# P21_HDMI_OUT.net
KiCad netlist of a schematic drawn in Altium Designer
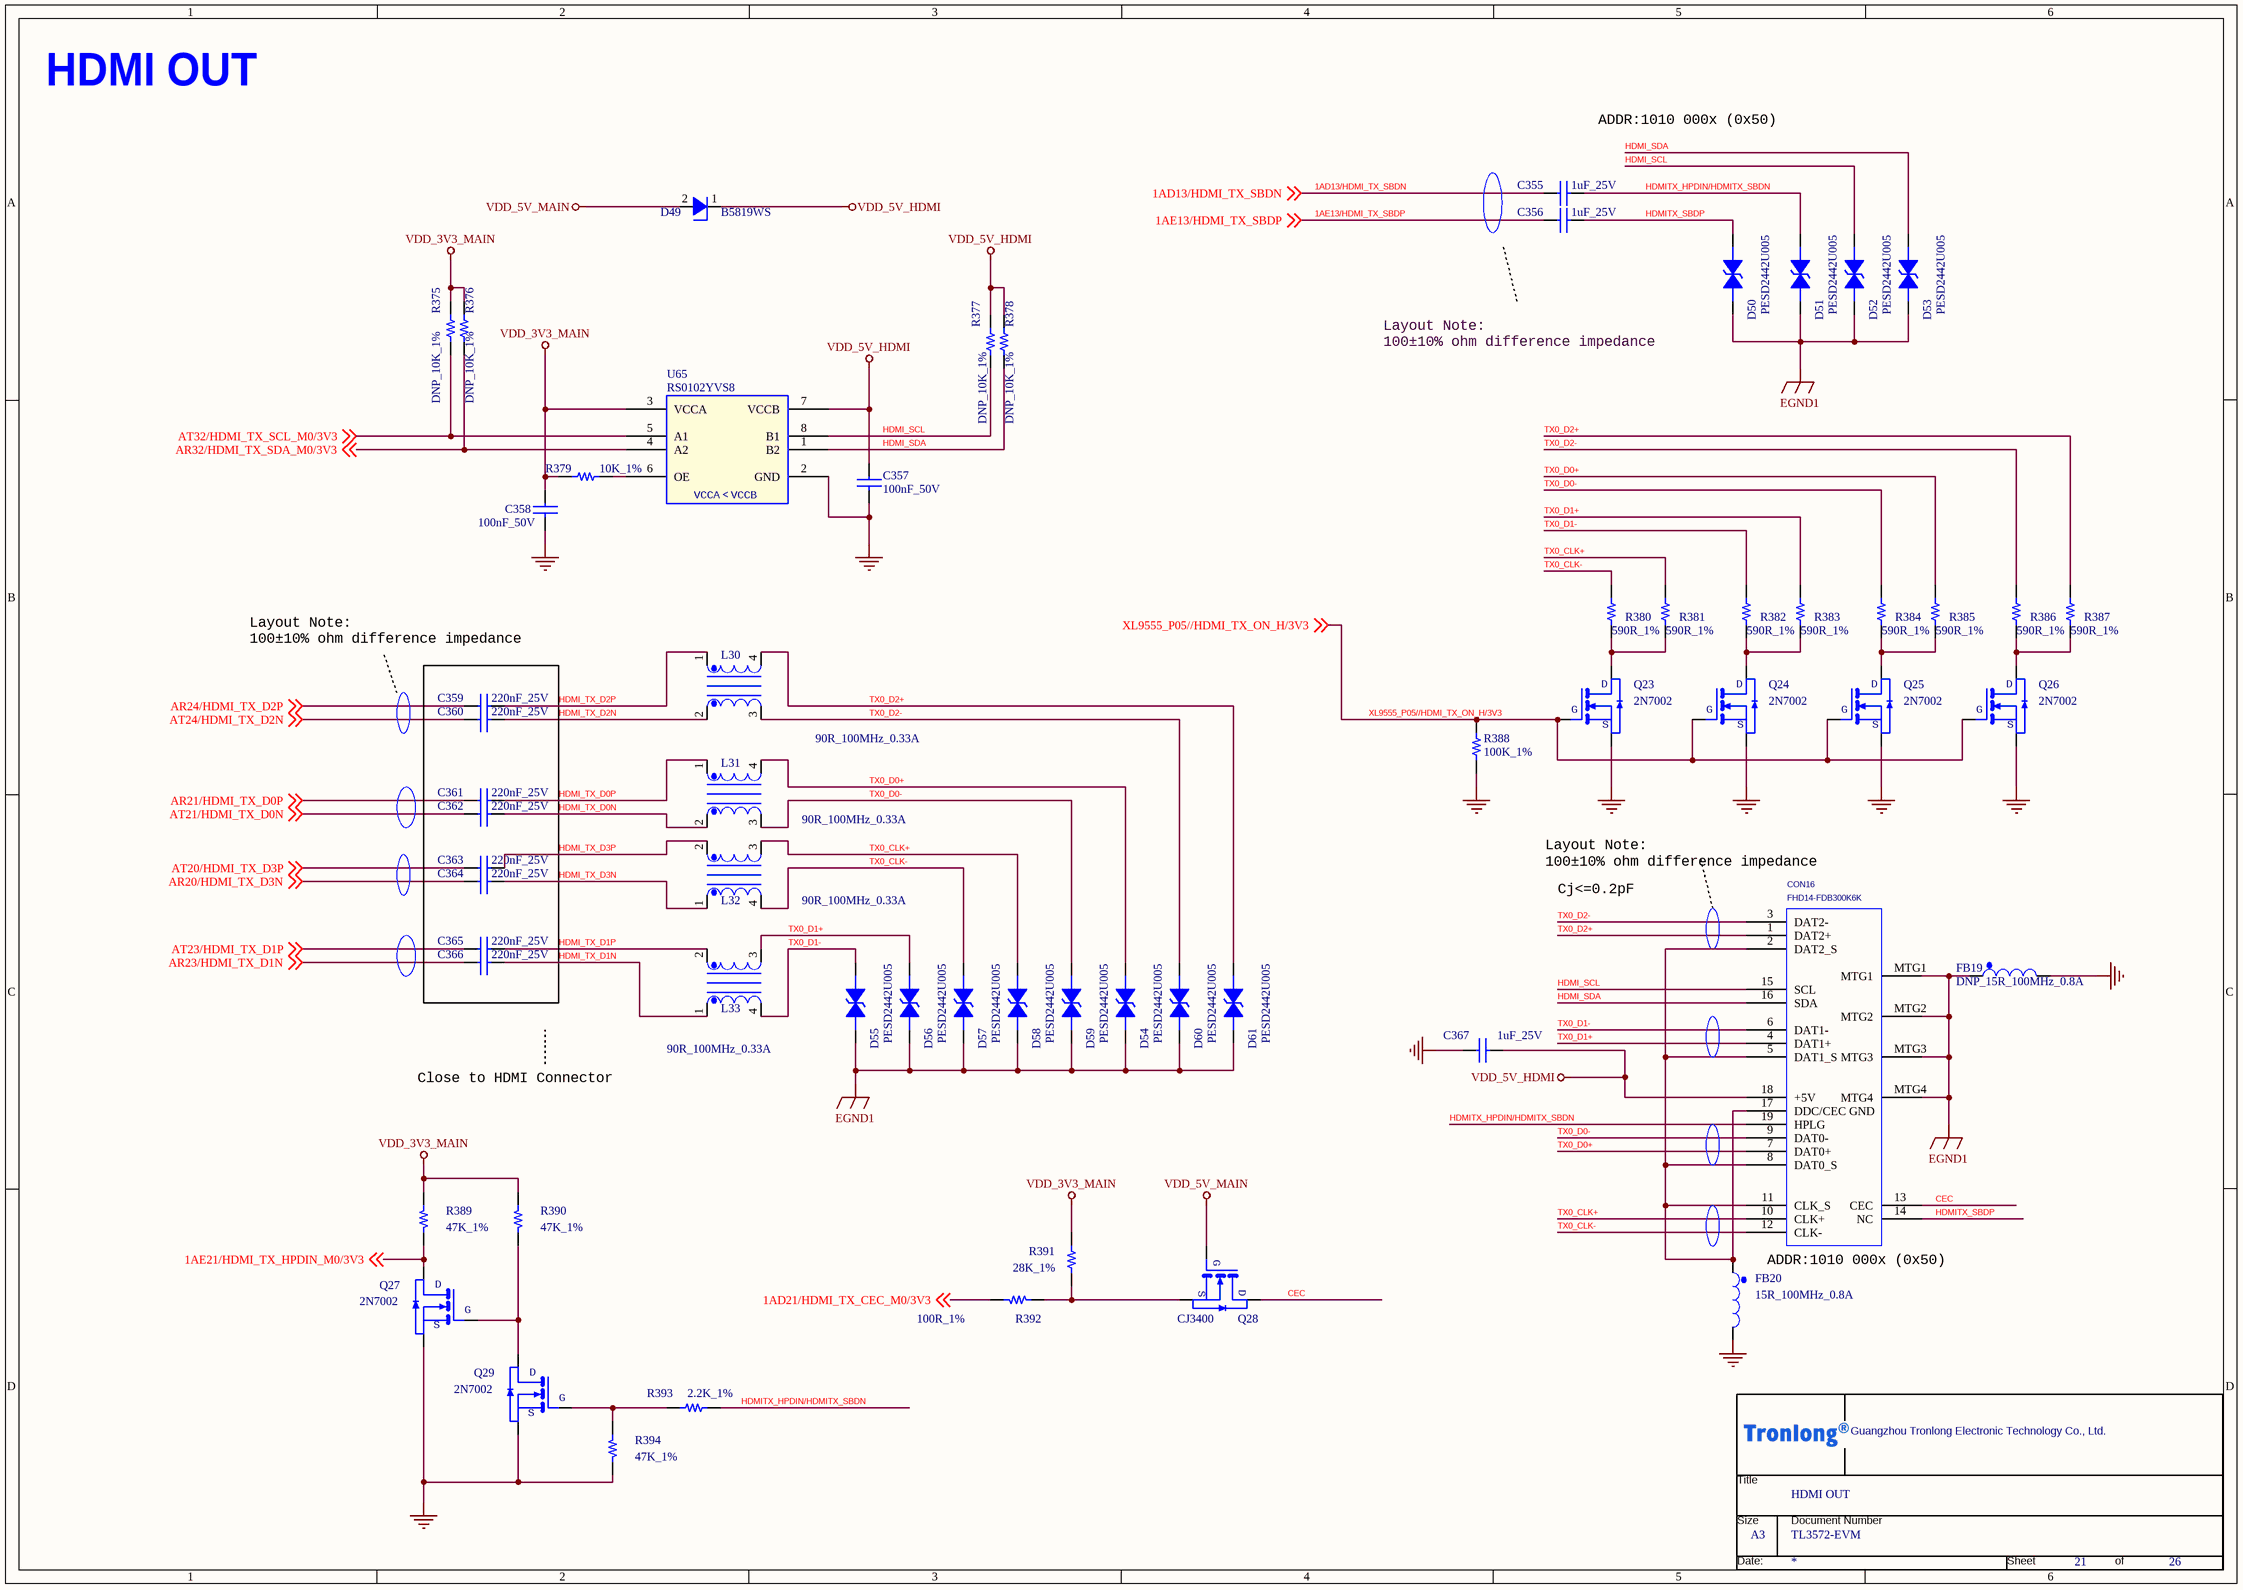
[diagram p0: P21_HDMI OUT.SchDoc]

(export (version "E")
  (design (tool "Eeschema 10.0.6"))
  (components
    (comp (ref "C355")
      (value "1uF_25V")
      (footprint "C0402")
      (description "贴片陶瓷电容,1uF,10%,25V,X5R")
      (fields (field (name "VOLTAGE") "50V") (field (name "MANUFACTURER PARTNUMBER") "0402X105K250NT"))
      (libsource (lib "*") (part "CAP NP_Dup3"))
    )
    (comp (ref "C356")
      (value "1uF_25V")
      (footprint "C0402")
      (description "贴片陶瓷电容,1uF,10%,25V,X5R")
      (fields (field (name "VOLTAGE") "50V") (field (name "MANUFACTURER PARTNUMBER") "0402X105K250NT"))
      (libsource (lib "*") (part "CAP NP_Dup3"))
    )
    (comp (ref "C357")
      (value "100nF_50V")
      (footprint "C0402")
      (description "贴片陶瓷电容,100nF,10%,50V,X7R")
      (fields
        (field (name "MANUFACTURER PARTNUMBER") "0402B104K500NT")
        (field (name "MANUFACTURER") "广东风华高新科技股份有限公司（FH）")
      )
      (libsource (lib "*") (part "CAP NP_Dup3"))
    )
    (comp (ref "C358")
      (value "100nF_50V")
      (footprint "C0402")
      (description "贴片陶瓷电容,100nF,10%,50V,X7R")
      (fields
        (field (name "MANUFACTURER PARTNUMBER") "0402B104K500NT")
        (field (name "MANUFACTURER") "广东风华高新科技股份有限公司（FH）")
      )
      (libsource (lib "*") (part "CAP NP_Dup3"))
    )
    (comp (ref "C359")
      (value "220nF_25V")
      (footprint "C0402")
      (description "贴片陶瓷电容,220nF,10%,25V,X5R")
      (fields
        (field (name "MANUFACTURER") "广东风华高新科技股份有限公司（FH）")
        (field (name "MANUFACTURER PARTNUMBER") "0402X224K250NT")
      )
      (libsource (lib "*") (part "CAP NP_Dup3"))
    )
    (comp (ref "C360")
      (value "220nF_25V")
      (footprint "C0402")
      (description "贴片陶瓷电容,220nF,10%,25V,X5R")
      (fields
        (field (name "MANUFACTURER") "广东风华高新科技股份有限公司（FH）")
        (field (name "MANUFACTURER PARTNUMBER") "0402X224K250NT")
      )
      (libsource (lib "*") (part "CAP NP_Dup3"))
    )
    (comp (ref "C361")
      (value "220nF_25V")
      (footprint "C0402")
      (description "贴片陶瓷电容,220nF,10%,25V,X5R")
      (fields (field (name "VOLTAGE") "50V") (field (name "MANUFACTURER PARTNUMBER") "0402X224K250NT"))
      (libsource (lib "*") (part "CAP NP_Dup3"))
    )
    (comp (ref "C362")
      (value "220nF_25V")
      (footprint "C0402")
      (description "贴片陶瓷电容,220nF,10%,25V,X5R")
      (fields (field (name "VOLTAGE") "50V") (field (name "MANUFACTURER PARTNUMBER") "0402X224K250NT"))
      (libsource (lib "*") (part "CAP NP_Dup3"))
    )
    (comp (ref "C363")
      (value "220nF_25V")
      (footprint "C0402")
      (description "贴片陶瓷电容,220nF,10%,25V,X5R")
      (fields (field (name "VOLTAGE") "50V") (field (name "MANUFACTURER PARTNUMBER") "0402X224K250NT"))
      (libsource (lib "*") (part "CAP NP_Dup3"))
    )
    (comp (ref "C364")
      (value "220nF_25V")
      (footprint "C0402")
      (description "贴片陶瓷电容,220nF,10%,25V,X5R")
      (fields (field (name "VOLTAGE") "50V") (field (name "MANUFACTURER PARTNUMBER") "0402X224K250NT"))
      (libsource (lib "*") (part "CAP NP_Dup3"))
    )
    (comp (ref "C365")
      (value "220nF_25V")
      (footprint "C0402")
      (description "贴片陶瓷电容,220nF,10%,25V,X5R")
      (fields (field (name "VOLTAGE") "50V") (field (name "MANUFACTURER PARTNUMBER") "0402X224K250NT"))
      (libsource (lib "*") (part "CAP NP_Dup3"))
    )
    (comp (ref "C366")
      (value "220nF_25V")
      (footprint "C0402")
      (description "贴片陶瓷电容,220nF,10%,25V,X5R")
      (fields (field (name "VOLTAGE") "50V") (field (name "MANUFACTURER PARTNUMBER") "0402X224K250NT"))
      (libsource (lib "*") (part "CAP NP_Dup3"))
    )
    (comp (ref "C367")
      (value "1uF_25V")
      (footprint "C0402")
      (description "贴片陶瓷电容,1uF,10%,25V,X5R")
      (fields
        (field (name "MANUFACTURER PARTNUMBER") "0402X105K250NT")
        (field (name "MANUFACTURER") "广东风华高新科技股份有限公司（FH）")
      )
      (libsource (lib "*") (part "CAP NP_Dup2"))
    )
    (comp (ref "CON16")
      (value "FHD14-FDB300K6K")
      (footprint "DIP_HDMI-A")
      (description "插件HDMI座,A型,19P,侧立")
      (fields (field (name "TIINTPARTNUMBER") "2C0085") (field (name "MFR") "FCI"))
      (libsource (lib "*") (part "2C_Conn_HDMI_TypeA"))
    )
    (comp (ref "D49")
      (value "B5819WS")
      (footprint "SOD-323")
      (description "肖特基二极管,VR=40V,IF=1A,VF=0.6V@1A")
      (fields (field (name "MFR") "On Semiconductor") (field (name "TIINTPARTNUMBER") "1E0013"))
      (libsource (lib "*") (part "DIODE-1N"))
    )
    (comp (ref "D50")
      (value "PESD2442U005")
      (footprint "ESD_0402")
      (description "ESD二极管,VRWM=24V,VBR=300V,一组,双向,8KV,15KV")
      (fields (field (name "MANUFACTURER") "上海雷卯电子科技有限公司（Leiditech）"))
      (libsource (lib "*") (part "DIODE-TRIG"))
    )
    (comp (ref "D51")
      (value "PESD2442U005")
      (footprint "ESD_0402")
      (description "ESD二极管,VRWM=24V,VBR=300V,一组,双向,8KV,15KV")
      (fields (field (name "MANUFACTURER") "上海雷卯电子科技有限公司（Leiditech）"))
      (libsource (lib "*") (part "DIODE-TRIG"))
    )
    (comp (ref "D52")
      (value "PESD2442U005")
      (footprint "ESD_0402")
      (description "ESD二极管,VRWM=24V,VBR=300V,一组,双向,8KV,15KV")
      (fields (field (name "MANUFACTURER") "上海雷卯电子科技有限公司（Leiditech）"))
      (libsource (lib "*") (part "DIODE-TRIG"))
    )
    (comp (ref "D53")
      (value "PESD2442U005")
      (footprint "ESD_0402")
      (description "ESD二极管,VRWM=24V,VBR=300V,一组,双向,8KV,15KV")
      (fields (field (name "MANUFACTURER") "上海雷卯电子科技有限公司（Leiditech）"))
      (libsource (lib "*") (part "DIODE-TRIG"))
    )
    (comp (ref "D54")
      (value "PESD2442U005")
      (footprint "ESD_0402")
      (description "ESD二极管,VRWM=24V,VBR=300V,一组,双向,8KV,15KV")
      (fields (field (name "MANUFACTURER") "上海雷卯电子科技有限公司（Leiditech）"))
      (libsource (lib "*") (part "DIODE-TRIG"))
    )
    (comp (ref "D55")
      (value "PESD2442U005")
      (footprint "ESD_0402")
      (description "ESD二极管,VRWM=24V,VBR=300V,一组,双向,8KV,15KV")
      (fields (field (name "MANUFACTURER") "上海雷卯电子科技有限公司（Leiditech）"))
      (libsource (lib "*") (part "DIODE-TRIG"))
    )
    (comp (ref "D56")
      (value "PESD2442U005")
      (footprint "ESD_0402")
      (description "ESD二极管,VRWM=24V,VBR=300V,一组,双向,8KV,15KV")
      (fields (field (name "MANUFACTURER") "上海雷卯电子科技有限公司（Leiditech）"))
      (libsource (lib "*") (part "DIODE-TRIG"))
    )
    (comp (ref "D57")
      (value "PESD2442U005")
      (footprint "ESD_0402")
      (description "ESD二极管,VRWM=24V,VBR=300V,一组,双向,8KV,15KV")
      (fields (field (name "MANUFACTURER") "上海雷卯电子科技有限公司（Leiditech）"))
      (libsource (lib "*") (part "DIODE-TRIG"))
    )
    (comp (ref "D58")
      (value "PESD2442U005")
      (footprint "ESD_0402")
      (description "ESD二极管,VRWM=24V,VBR=300V,一组,双向,8KV,15KV")
      (fields (field (name "MANUFACTURER") "上海雷卯电子科技有限公司（Leiditech）"))
      (libsource (lib "*") (part "DIODE-TRIG"))
    )
    (comp (ref "D59")
      (value "PESD2442U005")
      (footprint "ESD_0402")
      (description "ESD二极管,VRWM=24V,VBR=300V,一组,双向,8KV,15KV")
      (fields (field (name "MANUFACTURER") "上海雷卯电子科技有限公司（Leiditech）"))
      (libsource (lib "*") (part "DIODE-TRIG"))
    )
    (comp (ref "D60")
      (value "PESD2442U005")
      (footprint "ESD_0402")
      (description "ESD二极管,VRWM=24V,VBR=300V,一组,双向,8KV,15KV")
      (fields (field (name "MANUFACTURER") "上海雷卯电子科技有限公司（Leiditech）"))
      (libsource (lib "*") (part "DIODE-TRIG"))
    )
    (comp (ref "D61")
      (value "PESD2442U005")
      (footprint "ESD_0402")
      (description "ESD二极管,VRWM=24V,VBR=300V,一组,双向,8KV,15KV")
      (fields (field (name "MANUFACTURER") "上海雷卯电子科技有限公司（Leiditech）"))
      (libsource (lib "*") (part "DIODE-TRIG"))
    )
    (comp (ref "FB19")
      (value "DNP_15R_100MHz_0.8A")
      (footprint "L0603")
      (description "磁珠,100mΩ,0.8A,15R@100MHz")
      (fields
        (field (name "MANUFACTURER") "广东风华高新科技股份有限公司(FH)")
        (field (name "MANUFACTURER PARTNUMBER") "CBG160808U150T")
      )
      (libsource (lib "*") (part "FB_0"))
    )
    (comp (ref "FB20")
      (value "15R_100MHz_0.8A")
      (footprint "L0603")
      (description "磁珠,100mΩ,0.8A,15R@100MHz")
      (fields
        (field (name "MANUFACTURER PARTNUMBER") "CBG160808U150T")
        (field (name "MANUFACTURER") "广东风华高新科技股份有限公司(FH)")
      )
      (libsource (lib "*") (part "FB_0"))
    )
    (comp (ref "L30")
      (value "90R_100MHz_0.33A")
      (footprint "SMD-L2012M-4P")
      (description "贴片共模电感,350mΩ,0.33A,50V,90Ω@100MHz")
      (fields
        (field (name "MANUFACTURER") "深圳顺络电子股份有限公司（Sunlord）")
        (field (name "MANUFACTURER PARTNUMBER") "SDCW2012-2-900TF")
      )
      (libsource (lib "") (part "TFR_AXA_A_1_1"))
    )
    (comp (ref "L31")
      (value "90R_100MHz_0.33A")
      (footprint "SMD-L2012M-4P")
      (description "贴片共模电感,350mΩ,0.33A,50V,90Ω@100MHz")
      (fields
        (field (name "MANUFACTURER") "深圳顺络电子股份有限公司（Sunlord）")
        (field (name "MANUFACTURER PARTNUMBER") "SDCW2012-2-900TF")
      )
      (libsource (lib "") (part "TFR_AXA_A_1_1"))
    )
    (comp (ref "L32")
      (value "90R_100MHz_0.33A")
      (footprint "SMD-L2012M-4P")
      (description "贴片共模电感,350mΩ,0.33A,50V,90Ω@100MHz")
      (fields
        (field (name "MANUFACTURER PARTNUMBER") "SDCW2012-2-900TF")
        (field (name "MANUFACTURER") "深圳顺络电子股份有限公司（Sunlord）")
      )
      (libsource (lib "*") (part "TFR_AXA_A_1"))
    )
    (comp (ref "L33")
      (value "90R_100MHz_0.33A")
      (footprint "SMD-L2012M-4P")
      (description "贴片共模电感,350mΩ,0.33A,50V,90Ω@100MHz")
      (fields
        (field (name "MANUFACTURER") "深圳顺络电子股份有限公司（Sunlord）")
        (field (name "MANUFACTURER PARTNUMBER") "SDCW2012-2-900TF")
      )
      (libsource (lib "*") (part "TFR_AXA_A_1"))
    )
    (comp (ref "Q23")
      (value "2N7002")
      (footprint "SOT23-3_DBZ3")
      (description "MOSFET,N沟道,VDSS=60V,VGSS=±20V,ID=0.115A,PD=0.225W,VGS(th)=1.6V")
      (fields (field (name "MANUFACTURER") "江苏长晶科技股份有限公司（JSCJ）"))
      (libsource (lib "*") (part "MMBT3904/SOT_1"))
    )
    (comp (ref "Q24")
      (value "2N7002")
      (footprint "SOT23-3_DBZ3")
      (description "MOSFET,N沟道,VDSS=60V,VGSS=±20V,ID=0.115A,PD=0.225W,VGS(th)=1.6V")
      (fields (field (name "MANUFACTURER") "江苏长晶科技股份有限公司（JSCJ）"))
      (libsource (lib "*") (part "MMBT3904/SOT_1"))
    )
    (comp (ref "Q25")
      (value "2N7002")
      (footprint "SOT23-3_DBZ3")
      (description "MOSFET,N沟道,VDSS=60V,VGSS=±20V,ID=0.115A,PD=0.225W,VGS(th)=1.6V")
      (fields (field (name "MANUFACTURER") "江苏长晶科技股份有限公司（JSCJ）"))
      (libsource (lib "*") (part "MMBT3904/SOT_1"))
    )
    (comp (ref "Q26")
      (value "2N7002")
      (footprint "SOT23-3_DBZ3")
      (description "MOSFET,N沟道,VDSS=60V,VGSS=±20V,ID=0.115A,PD=0.225W,VGS(th)=1.6V")
      (fields (field (name "MANUFACTURER") "江苏长晶科技股份有限公司（JSCJ）"))
      (libsource (lib "*") (part "MMBT3904/SOT_1"))
    )
    (comp (ref "Q27")
      (value "2N7002")
      (footprint "SOT23-3_DBZ3")
      (description "MOSFET,N沟道,VDSS=60V,VGSS=±20V,ID=0.115A,PD=0.225W,VGS(th)=1.6V")
      (fields (field (name "MANUFACTURER") "江苏长晶科技股份有限公司（JSCJ）"))
      (libsource (lib "*") (part "MMBT3904/SOT_1"))
    )
    (comp (ref "Q28")
      (value "CJ3400")
      (footprint "SOT23-3")
      (description "MOSFET,N沟道,VDSS=30V,VGSS=±12V,ID=5.8A,PD=0.35W,VGS(th)=1.4V")
      (fields (field (name "MANUFACTURER") "江苏长晶科技股份有限公司（JSCJ）"))
      (libsource (lib "*") (part "MOSFET N SOT"))
    )
    (comp (ref "Q29")
      (value "2N7002")
      (footprint "SOT23-3_DBZ3")
      (description "MOSFET,N沟道,VDSS=60V,VGSS=±20V,ID=0.115A,PD=0.225W,VGS(th)=1.6V")
      (fields (field (name "MANUFACTURER") "江苏长晶科技股份有限公司（JSCJ）"))
      (libsource (lib "*") (part "MMBT3904/SOT_1"))
    )
    (comp (ref "R375")
      (value "DNP_10K_1%")
      (footprint "R0402")
      (description "贴片电阻,10K,±1%,1/16W")
      (fields
        (field (name "MANUFACTURER") "广东风华高新科技股份有限公司（FH）")
        (field (name "MANUFACTURER PARTNUMBER") "RC-02K1002FT")
      )
      (libsource (lib "*") (part "Resistor_Dup4"))
    )
    (comp (ref "R376")
      (value "DNP_10K_1%")
      (footprint "R0402")
      (description "贴片电阻,10K,±1%,1/16W")
      (fields
        (field (name "MANUFACTURER") "广东风华高新科技股份有限公司（FH）")
        (field (name "MANUFACTURER PARTNUMBER") "RC-02K1002FT")
      )
      (libsource (lib "*") (part "Resistor_Dup4"))
    )
    (comp (ref "R377")
      (value "DNP_10K_1%")
      (footprint "R0402")
      (description "贴片电阻,10K,±1%,1/16W")
      (fields
        (field (name "MANUFACTURER PARTNUMBER") "RC-02K1002FT")
        (field (name "MANUFACTURER") "广东风华高新科技股份有限公司（FH）")
      )
      (libsource (lib "*") (part "Resistor_Dup4"))
    )
    (comp (ref "R378")
      (value "DNP_10K_1%")
      (footprint "R0402")
      (description "贴片电阻,10K,±1%,1/16W")
      (fields
        (field (name "MANUFACTURER PARTNUMBER") "RC-02K1002FT")
        (field (name "MANUFACTURER") "广东风华高新科技股份有限公司（FH）")
      )
      (libsource (lib "*") (part "Resistor_Dup4"))
    )
    (comp (ref "R379")
      (value "10K_1%")
      (footprint "R0402")
      (description "贴片电阻,10K,±1%,1/16W")
      (fields
        (field (name "MANUFACTURER PARTNUMBER") "RC-02K1002FT")
        (field (name "MANUFACTURER") "广东风华高新科技股份有限公司（FH）")
      )
      (libsource (lib "*") (part "Resistor_Dup4"))
    )
    (comp (ref "R380")
      (value "590R_1%")
      (footprint "R0402")
      (description "贴片电阻,590R,±1%,1/16W")
      (fields
        (field (name "MANUFACTURER") "广东风华高新科技股份有限公司（FH）")
        (field (name "MANUFACTURER PARTNUMBER") "RC-02K5900FT")
      )
      (libsource (lib "*") (part "Resistor_Dup4"))
    )
    (comp (ref "R381")
      (value "590R_1%")
      (footprint "R0402")
      (description "贴片电阻,590R,±1%,1/16W")
      (fields
        (field (name "MANUFACTURER PARTNUMBER") "RC-02K5900FT")
        (field (name "MANUFACTURER") "广东风华高新科技股份有限公司（FH）")
      )
      (libsource (lib "*") (part "Resistor_Dup4"))
    )
    (comp (ref "R382")
      (value "590R_1%")
      (footprint "R0402")
      (description "贴片电阻,590R,±1%,1/16W")
      (fields
        (field (name "MANUFACTURER PARTNUMBER") "RC-02K5900FT")
        (field (name "MANUFACTURER") "广东风华高新科技股份有限公司（FH）")
      )
      (libsource (lib "*") (part "Resistor_Dup4"))
    )
    (comp (ref "R383")
      (value "590R_1%")
      (footprint "R0402")
      (description "贴片电阻,590R,±1%,1/16W")
      (fields
        (field (name "MANUFACTURER PARTNUMBER") "RC-02K5900FT")
        (field (name "MANUFACTURER") "广东风华高新科技股份有限公司（FH）")
      )
      (libsource (lib "*") (part "Resistor_Dup4"))
    )
    (comp (ref "R384")
      (value "590R_1%")
      (footprint "R0402")
      (description "贴片电阻,590R,±1%,1/16W")
      (fields
        (field (name "MANUFACTURER PARTNUMBER") "RC-02K5900FT")
        (field (name "MANUFACTURER") "广东风华高新科技股份有限公司（FH）")
      )
      (libsource (lib "*") (part "Resistor_Dup4"))
    )
    (comp (ref "R385")
      (value "590R_1%")
      (footprint "R0402")
      (description "贴片电阻,590R,±1%,1/16W")
      (fields
        (field (name "MANUFACTURER") "广东风华高新科技股份有限公司（FH）")
        (field (name "MANUFACTURER PARTNUMBER") "RC-02K5900FT")
      )
      (libsource (lib "*") (part "Resistor_Dup4"))
    )
    (comp (ref "R386")
      (value "590R_1%")
      (footprint "R0402")
      (description "贴片电阻,590R,±1%,1/16W")
      (fields
        (field (name "MANUFACTURER") "广东风华高新科技股份有限公司（FH）")
        (field (name "MANUFACTURER PARTNUMBER") "RC-02K5900FT")
      )
      (libsource (lib "*") (part "Resistor_Dup4"))
    )
    (comp (ref "R387")
      (value "590R_1%")
      (footprint "R0402")
      (description "贴片电阻,590R,±1%,1/16W")
      (fields
        (field (name "MANUFACTURER") "广东风华高新科技股份有限公司（FH）")
        (field (name "MANUFACTURER PARTNUMBER") "RC-02K5900FT")
      )
      (libsource (lib "*") (part "Resistor_Dup4"))
    )
    (comp (ref "R388")
      (value "100K_1%")
      (footprint "R0402")
      (description "RC0402FR-07100KL,0402WGF1003TCE")
      (fields (field (name "TOLERANCE") "5%") (field (name "PART NUMBER") "737-00-3066"))
      (libsource (lib "*") (part "Resistor_Dup4"))
    )
    (comp (ref "R389")
      (value "47K_1%")
      (footprint "R0402")
      (description "贴片电阻,47K,±1%,1/16W")
      (fields
        (field (name "MANUFACTURER") "广东风华高新科技股份有限公司（FH）")
        (field (name "MANUFACTURER PARTNUMBER") "RC-02K4702FT")
      )
      (libsource (lib "*") (part "Resistor_Dup4"))
    )
    (comp (ref "R390")
      (value "47K_1%")
      (footprint "R0402")
      (description "贴片电阻,47K,±1%,1/16W")
      (fields
        (field (name "MANUFACTURER PARTNUMBER") "RC-02K4702FT")
        (field (name "MANUFACTURER") "广东风华高新科技股份有限公司（FH）")
      )
      (libsource (lib "*") (part "Resistor_Dup4"))
    )
    (comp (ref "R391")
      (value "28K_1%")
      (footprint "R0402")
      (description "贴片电阻,28K,±1%,1/16W")
      (fields
        (field (name "MANUFACTURER PARTNUMBER") "RC-02K2802FT")
        (field (name "MANUFACTURER") "广东风华高新科技股份有限公司（FH）")
      )
      (libsource (lib "*") (part "Resistor_Dup3"))
    )
    (comp (ref "R392")
      (value "100R_1%")
      (footprint "R0402")
      (description "贴片电阻,100R,±1%,1/16W")
      (fields
        (field (name "MANUFACTURER") "广东风华高新科技股份有限公司（FH）")
        (field (name "MANUFACTURER PARTNUMBER") "RC-02K1000FT")
      )
      (libsource (lib "*") (part "Resistor_Dup3"))
    )
    (comp (ref "R393")
      (value "2.2K_1%")
      (footprint "R0603")
      (description "贴片电阻,2.2K,±1%,1/10W")
      (fields
        (field (name "MANUFACTURER") "广东风华高新科技股份有限公司（FH）")
        (field (name "MANUFACTURER PARTNUMBER") "RS-03K2201FT")
      )
      (libsource (lib "*") (part "Resistor_Dup4"))
    )
    (comp (ref "R394")
      (value "47K_1%")
      (footprint "R0402")
      (description "贴片电阻,47K,±1%,1/16W")
      (fields
        (field (name "MANUFACTURER") "广东风华高新科技股份有限公司（FH）")
        (field (name "MANUFACTURER PARTNUMBER") "RC-02K4702FT")
      )
      (libsource (lib "*") (part "Resistor_Dup4"))
    )
    (comp (ref "U65")
      (value "RS0102YVS8")
      (footprint "SOP8-20-91")
      (description "2位双向电平转换器")
      (fields (field (name "MANUFACTURER") "江苏润石科技有限公司（RUNIC）"))
      (libsource (lib "*") (part "TXS0102DCUR_0"))
    )
  )
  (nets
    (net (code "1") (name "/CEC") (class "Default")
      (node (ref "CON16") (pin "13") (pinfunction "CEC_13") (pintype "passive"))
      (node (ref "Q28") (pin "3") (pinfunction "C_3") (pintype "passive"))
    )
    (net (code "2") (name "/HDMITX_HPDIN{slash}HDMITX_SBDN") (class "Default")
      (node (ref "C355") (pin "2") (pinfunction "2_2") (pintype "passive"))
      (node (ref "CON16") (pin "19") (pinfunction "HPLG_19") (pintype "passive"))
      (node (ref "D51") (pin "1") (pinfunction "1_1") (pintype "passive"))
      (node (ref "R393") (pin "2") (pinfunction "2_2") (pintype "passive"))
    )
    (net (code "3") (name "/HDMITX_SBDP") (class "Default")
      (node (ref "C356") (pin "2") (pinfunction "2_2") (pintype "passive"))
      (node (ref "CON16") (pin "14") (pinfunction "NC_14") (pintype "passive"))
      (node (ref "D50") (pin "1") (pinfunction "1_1") (pintype "passive"))
    )
    (net (code "4") (name "/HDMI_SCL") (class "Default")
      (node (ref "CON16") (pin "15") (pinfunction "SCL_15") (pintype "passive"))
      (node (ref "D52") (pin "1") (pinfunction "1_1") (pintype "passive"))
      (node (ref "R377") (pin "2") (pinfunction "2_2") (pintype "passive"))
      (node (ref "U65") (pin "8") (pinfunction "B1_8") (pintype "passive"))
    )
    (net (code "5") (name "/HDMI_SDA") (class "Default")
      (node (ref "CON16") (pin "16") (pinfunction "SDA_16") (pintype "passive"))
      (node (ref "D53") (pin "1") (pinfunction "1_1") (pintype "passive"))
      (node (ref "R378") (pin "2") (pinfunction "2_2") (pintype "passive"))
      (node (ref "U65") (pin "1") (pinfunction "B2_1") (pintype "passive"))
    )
    (net (code "6") (name "/HDMI_TX_D0N") (class "Default")
      (node (ref "C362") (pin "2") (pinfunction "2_2") (pintype "passive"))
      (node (ref "L31") (pin "2") (pinfunction "2_2") (pintype "passive"))
    )
    (net (code "7") (name "/HDMI_TX_D0P") (class "Default")
      (node (ref "C361") (pin "2") (pinfunction "2_2") (pintype "passive"))
      (node (ref "L31") (pin "1") (pinfunction "1_1") (pintype "passive"))
    )
    (net (code "8") (name "/HDMI_TX_D1N") (class "Default")
      (node (ref "C366") (pin "2") (pinfunction "2_2") (pintype "passive"))
      (node (ref "L33") (pin "1") (pinfunction "1_1") (pintype "passive"))
    )
    (net (code "9") (name "/HDMI_TX_D1P") (class "Default")
      (node (ref "C365") (pin "2") (pinfunction "2_2") (pintype "passive"))
      (node (ref "L33") (pin "2") (pinfunction "2_2") (pintype "passive"))
    )
    (net (code "10") (name "/HDMI_TX_D2N") (class "Default")
      (node (ref "C360") (pin "2") (pinfunction "2_2") (pintype "passive"))
      (node (ref "L30") (pin "2") (pinfunction "2_2") (pintype "passive"))
    )
    (net (code "11") (name "/HDMI_TX_D2P") (class "Default")
      (node (ref "C359") (pin "2") (pinfunction "2_2") (pintype "passive"))
      (node (ref "L30") (pin "1") (pinfunction "1_1") (pintype "passive"))
    )
    (net (code "12") (name "/HDMI_TX_D3N") (class "Default")
      (node (ref "C364") (pin "2") (pinfunction "2_2") (pintype "passive"))
      (node (ref "L32") (pin "1") (pinfunction "1_1") (pintype "passive"))
    )
    (net (code "13") (name "/HDMI_TX_D3P") (class "Default")
      (node (ref "C363") (pin "2") (pinfunction "2_2") (pintype "passive"))
      (node (ref "L32") (pin "2") (pinfunction "2_2") (pintype "passive"))
    )
    (net (code "14") (name "/TX0_CLK+") (class "Default")
      (node (ref "CON16") (pin "10") (pinfunction "CLK+_10") (pintype "passive"))
      (node (ref "D58") (pin "1") (pinfunction "1_1") (pintype "passive"))
      (node (ref "L32") (pin "3") (pinfunction "3_3") (pintype "passive"))
      (node (ref "R381") (pin "1") (pinfunction "1_1") (pintype "passive"))
    )
    (net (code "15") (name "/TX0_CLK-") (class "Default")
      (node (ref "CON16") (pin "12") (pinfunction "CLK-_12") (pintype "passive"))
      (node (ref "D57") (pin "1") (pinfunction "1_1") (pintype "passive"))
      (node (ref "L32") (pin "4") (pinfunction "4_4") (pintype "passive"))
      (node (ref "R380") (pin "1") (pinfunction "1_1") (pintype "passive"))
    )
    (net (code "16") (name "/TX0_D0+") (class "Default")
      (node (ref "CON16") (pin "7") (pinfunction "DAT0+_7") (pintype "passive"))
      (node (ref "D54") (pin "1") (pinfunction "1_1") (pintype "passive"))
      (node (ref "L31") (pin "4") (pinfunction "4_4") (pintype "passive"))
      (node (ref "R385") (pin "1") (pinfunction "1_1") (pintype "passive"))
    )
    (net (code "17") (name "/TX0_D0-") (class "Default")
      (node (ref "CON16") (pin "9") (pinfunction "DAT0-_9") (pintype "passive"))
      (node (ref "D59") (pin "1") (pinfunction "1_1") (pintype "passive"))
      (node (ref "L31") (pin "3") (pinfunction "3_3") (pintype "passive"))
      (node (ref "R384") (pin "1") (pinfunction "1_1") (pintype "passive"))
    )
    (net (code "18") (name "/TX0_D1+") (class "Default")
      (node (ref "CON16") (pin "4") (pinfunction "DAT1+_4") (pintype "passive"))
      (node (ref "D56") (pin "1") (pinfunction "1_1") (pintype "passive"))
      (node (ref "L33") (pin "3") (pinfunction "3_3") (pintype "passive"))
      (node (ref "R383") (pin "1") (pinfunction "1_1") (pintype "passive"))
    )
    (net (code "19") (name "/TX0_D1-") (class "Default")
      (node (ref "CON16") (pin "6") (pinfunction "DAT1-_6") (pintype "passive"))
      (node (ref "D55") (pin "1") (pinfunction "1_1") (pintype "passive"))
      (node (ref "L33") (pin "4") (pinfunction "4_4") (pintype "passive"))
      (node (ref "R382") (pin "1") (pinfunction "1_1") (pintype "passive"))
    )
    (net (code "20") (name "/TX0_D2+") (class "Default")
      (node (ref "CON16") (pin "1") (pinfunction "DAT2+_1") (pintype "passive"))
      (node (ref "D61") (pin "1") (pinfunction "1_1") (pintype "passive"))
      (node (ref "L30") (pin "4") (pinfunction "4_4") (pintype "passive"))
      (node (ref "R387") (pin "1") (pinfunction "1_1") (pintype "passive"))
    )
    (net (code "21") (name "/TX0_D2-") (class "Default")
      (node (ref "CON16") (pin "3") (pinfunction "DAT2-_3") (pintype "passive"))
      (node (ref "D60") (pin "1") (pinfunction "1_1") (pintype "passive"))
      (node (ref "L30") (pin "3") (pinfunction "3_3") (pintype "passive"))
      (node (ref "R386") (pin "1") (pinfunction "1_1") (pintype "passive"))
    )
    (net (code "22") (name "1AD13{slash}HDMI_TX_SBDN") (class "Default")
      (node (ref "C355") (pin "1") (pinfunction "1_1") (pintype "passive"))
    )
    (net (code "23") (name "1AD21{slash}HDMI_TX_CEC_M0{slash}3V3") (class "Default")
      (node (ref "R392") (pin "2") (pinfunction "2_2") (pintype "passive"))
    )
    (net (code "24") (name "1AE13{slash}HDMI_TX_SBDP") (class "Default")
      (node (ref "C356") (pin "1") (pinfunction "1_1") (pintype "passive"))
    )
    (net (code "25") (name "1AE21{slash}HDMI_TX_HPDIN_M0{slash}3V3") (class "Default")
      (node (ref "Q27") (pin "3") (pinfunction "C_3") (pintype "passive"))
      (node (ref "R389") (pin "2") (pinfunction "2_2") (pintype "passive"))
    )
    (net (code "26") (name "AR20{slash}HDMI_TX_D3N") (class "Default")
      (node (ref "C364") (pin "1") (pinfunction "1_1") (pintype "passive"))
    )
    (net (code "27") (name "AR21{slash}HDMI_TX_D0P") (class "Default")
      (node (ref "C361") (pin "1") (pinfunction "1_1") (pintype "passive"))
    )
    (net (code "28") (name "AR23{slash}HDMI_TX_D1N") (class "Default")
      (node (ref "C366") (pin "1") (pinfunction "1_1") (pintype "passive"))
    )
    (net (code "29") (name "AR24{slash}HDMI_TX_D2P") (class "Default")
      (node (ref "C359") (pin "1") (pinfunction "1_1") (pintype "passive"))
    )
    (net (code "30") (name "AR32{slash}HDMI_TX_SDA_M0{slash}3V3") (class "Default")
      (node (ref "R376") (pin "2") (pinfunction "2_2") (pintype "passive"))
      (node (ref "U65") (pin "4") (pinfunction "A2_4") (pintype "passive"))
    )
    (net (code "31") (name "AT20{slash}HDMI_TX_D3P") (class "Default")
      (node (ref "C363") (pin "1") (pinfunction "1_1") (pintype "passive"))
    )
    (net (code "32") (name "AT21{slash}HDMI_TX_D0N") (class "Default")
      (node (ref "C362") (pin "1") (pinfunction "1_1") (pintype "passive"))
    )
    (net (code "33") (name "AT23{slash}HDMI_TX_D1P") (class "Default")
      (node (ref "C365") (pin "1") (pinfunction "1_1") (pintype "passive"))
    )
    (net (code "34") (name "AT24{slash}HDMI_TX_D2N") (class "Default")
      (node (ref "C360") (pin "1") (pinfunction "1_1") (pintype "passive"))
    )
    (net (code "35") (name "AT32{slash}HDMI_TX_SCL_M0{slash}3V3") (class "Default")
      (node (ref "R375") (pin "2") (pinfunction "2_2") (pintype "passive"))
      (node (ref "U65") (pin "5") (pinfunction "A1_5") (pintype "passive"))
    )
    (net (code "36") (name "EGND1") (class "Default")
      (node (ref "CON16") (pin "MTG1") (pinfunction "MTG1_MTG1") (pintype "power_in"))
      (node (ref "CON16") (pin "MTG2") (pinfunction "MTG2_MTG2") (pintype "power_in"))
      (node (ref "CON16") (pin "MTG3") (pinfunction "MTG3_MTG3") (pintype "power_in"))
      (node (ref "CON16") (pin "MTG4") (pinfunction "MTG4_MTG4") (pintype "power_in"))
      (node (ref "D50") (pin "2") (pinfunction "2_2") (pintype "passive"))
      (node (ref "D51") (pin "2") (pinfunction "2_2") (pintype "passive"))
      (node (ref "D52") (pin "2") (pinfunction "2_2") (pintype "passive"))
      (node (ref "D53") (pin "2") (pinfunction "2_2") (pintype "passive"))
      (node (ref "D54") (pin "2") (pinfunction "2_2") (pintype "passive"))
      (node (ref "D55") (pin "2") (pinfunction "2_2") (pintype "passive"))
      (node (ref "D56") (pin "2") (pinfunction "2_2") (pintype "passive"))
      (node (ref "D57") (pin "2") (pinfunction "2_2") (pintype "passive"))
      (node (ref "D58") (pin "2") (pinfunction "2_2") (pintype "passive"))
      (node (ref "D59") (pin "2") (pinfunction "2_2") (pintype "passive"))
      (node (ref "D60") (pin "2") (pinfunction "2_2") (pintype "passive"))
      (node (ref "D61") (pin "2") (pinfunction "2_2") (pintype "passive"))
      (node (ref "FB19") (pin "1") (pinfunction "1_1") (pintype "passive"))
    )
    (net (code "37") (name "GND") (class "Default")
      (node (ref "C357") (pin "2") (pinfunction "2_2") (pintype "passive"))
      (node (ref "C358") (pin "2") (pinfunction "2_2") (pintype "passive"))
      (node (ref "C367") (pin "1") (pinfunction "1_1") (pintype "passive"))
      (node (ref "FB19") (pin "2") (pinfunction "2_2") (pintype "passive"))
      (node (ref "FB20") (pin "2") (pinfunction "2_2") (pintype "passive"))
      (node (ref "Q23") (pin "2") (pinfunction "E_2") (pintype "passive"))
      (node (ref "Q24") (pin "2") (pinfunction "E_2") (pintype "passive"))
      (node (ref "Q25") (pin "2") (pinfunction "E_2") (pintype "passive"))
      (node (ref "Q26") (pin "2") (pinfunction "E_2") (pintype "passive"))
      (node (ref "Q27") (pin "2") (pinfunction "E_2") (pintype "passive"))
      (node (ref "Q29") (pin "2") (pinfunction "E_2") (pintype "passive"))
      (node (ref "R388") (pin "1") (pinfunction "1_1") (pintype "passive"))
      (node (ref "R394") (pin "2") (pinfunction "2_2") (pintype "passive"))
      (node (ref "U65") (pin "2") (pinfunction "GND_2") (pintype "passive"))
    )
    (net (code "38") (name "Net-(CON16-CLK_S)") (class "Default")
      (node (ref "CON16") (pin "11") (pinfunction "CLK_S_11") (pintype "passive"))
      (node (ref "CON16") (pin "17") (pinfunction "DDC/CEC_GND_17") (pintype "passive"))
      (node (ref "CON16") (pin "2") (pinfunction "DAT2_S_2") (pintype "passive"))
      (node (ref "CON16") (pin "5") (pinfunction "DAT1_S_5") (pintype "passive"))
      (node (ref "CON16") (pin "8") (pinfunction "DAT0_S_8") (pintype "passive"))
      (node (ref "FB20") (pin "1") (pinfunction "1_1") (pintype "passive"))
    )
    (net (code "39") (name "Net-(Q23-C)") (class "Default")
      (node (ref "Q23") (pin "3") (pinfunction "C_3") (pintype "passive"))
      (node (ref "R380") (pin "2") (pinfunction "2_2") (pintype "passive"))
      (node (ref "R381") (pin "2") (pinfunction "2_2") (pintype "passive"))
    )
    (net (code "40") (name "Net-(Q24-C)") (class "Default")
      (node (ref "Q24") (pin "3") (pinfunction "C_3") (pintype "passive"))
      (node (ref "R382") (pin "2") (pinfunction "2_2") (pintype "passive"))
      (node (ref "R383") (pin "2") (pinfunction "2_2") (pintype "passive"))
    )
    (net (code "41") (name "Net-(Q25-C)") (class "Default")
      (node (ref "Q25") (pin "3") (pinfunction "C_3") (pintype "passive"))
      (node (ref "R384") (pin "2") (pinfunction "2_2") (pintype "passive"))
      (node (ref "R385") (pin "2") (pinfunction "2_2") (pintype "passive"))
    )
    (net (code "42") (name "Net-(Q26-C)") (class "Default")
      (node (ref "Q26") (pin "3") (pinfunction "C_3") (pintype "passive"))
      (node (ref "R386") (pin "2") (pinfunction "2_2") (pintype "passive"))
      (node (ref "R387") (pin "2") (pinfunction "2_2") (pintype "passive"))
    )
    (net (code "43") (name "Net-(Q27-B)") (class "Default")
      (node (ref "Q27") (pin "1") (pinfunction "B_1") (pintype "passive"))
      (node (ref "Q29") (pin "3") (pinfunction "C_3") (pintype "passive"))
      (node (ref "R390") (pin "2") (pinfunction "2_2") (pintype "passive"))
    )
    (net (code "44") (name "Net-(Q28-E)") (class "Default")
      (node (ref "Q28") (pin "2") (pinfunction "E_2") (pintype "passive"))
      (node (ref "R391") (pin "1") (pinfunction "1_1") (pintype "passive"))
      (node (ref "R392") (pin "1") (pinfunction "1_1") (pintype "passive"))
    )
    (net (code "45") (name "Net-(Q29-B)") (class "Default")
      (node (ref "Q29") (pin "1") (pinfunction "B_1") (pintype "passive"))
      (node (ref "R393") (pin "1") (pinfunction "1_1") (pintype "passive"))
      (node (ref "R394") (pin "1") (pinfunction "1_1") (pintype "passive"))
    )
    (net (code "46") (name "Net-(U65-OE)") (class "Default")
      (node (ref "R379") (pin "2") (pinfunction "2_2") (pintype "passive"))
      (node (ref "U65") (pin "6") (pinfunction "OE_6") (pintype "passive"))
    )
    (net (code "47") (name "VDD_3V3_MAIN") (class "Default")
      (node (ref "C358") (pin "1") (pinfunction "1_1") (pintype "passive"))
      (node (ref "R375") (pin "1") (pinfunction "1_1") (pintype "passive"))
      (node (ref "R376") (pin "1") (pinfunction "1_1") (pintype "passive"))
      (node (ref "R379") (pin "1") (pinfunction "1_1") (pintype "passive"))
      (node (ref "R389") (pin "1") (pinfunction "1_1") (pintype "passive"))
      (node (ref "R390") (pin "1") (pinfunction "1_1") (pintype "passive"))
      (node (ref "R391") (pin "2") (pinfunction "2_2") (pintype "passive"))
      (node (ref "U65") (pin "3") (pinfunction "VCCA_3") (pintype "passive"))
    )
    (net (code "48") (name "VDD_5V_HDMI") (class "Default")
      (node (ref "C357") (pin "1") (pinfunction "1_1") (pintype "passive"))
      (node (ref "C367") (pin "2") (pinfunction "2_2") (pintype "passive"))
      (node (ref "CON16") (pin "18") (pinfunction "+5V_18") (pintype "passive"))
      (node (ref "D49") (pin "1") (pinfunction "Cathode_1") (pintype "passive"))
      (node (ref "R377") (pin "1") (pinfunction "1_1") (pintype "passive"))
      (node (ref "R378") (pin "1") (pinfunction "1_1") (pintype "passive"))
      (node (ref "U65") (pin "7") (pinfunction "VCCB_7") (pintype "passive"))
    )
    (net (code "49") (name "VDD_5V_MAIN") (class "Default")
      (node (ref "D49") (pin "2") (pinfunction "Anode_2") (pintype "passive"))
      (node (ref "Q28") (pin "1") (pinfunction "B_1") (pintype "passive"))
    )
    (net (code "50") (name "XL9555_P05{slash}{slash}HDMI_TX_ON_H{slash}3V3") (class "Default")
      (node (ref "Q23") (pin "1") (pinfunction "B_1") (pintype "passive"))
      (node (ref "Q24") (pin "1") (pinfunction "B_1") (pintype "passive"))
      (node (ref "Q25") (pin "1") (pinfunction "B_1") (pintype "passive"))
      (node (ref "Q26") (pin "1") (pinfunction "B_1") (pintype "passive"))
      (node (ref "R388") (pin "2") (pinfunction "2_2") (pintype "passive"))
    )
  )
)
